# RaspberryPi4_shield.net
KiCad netlist of a schematic drawn in Altium Designer
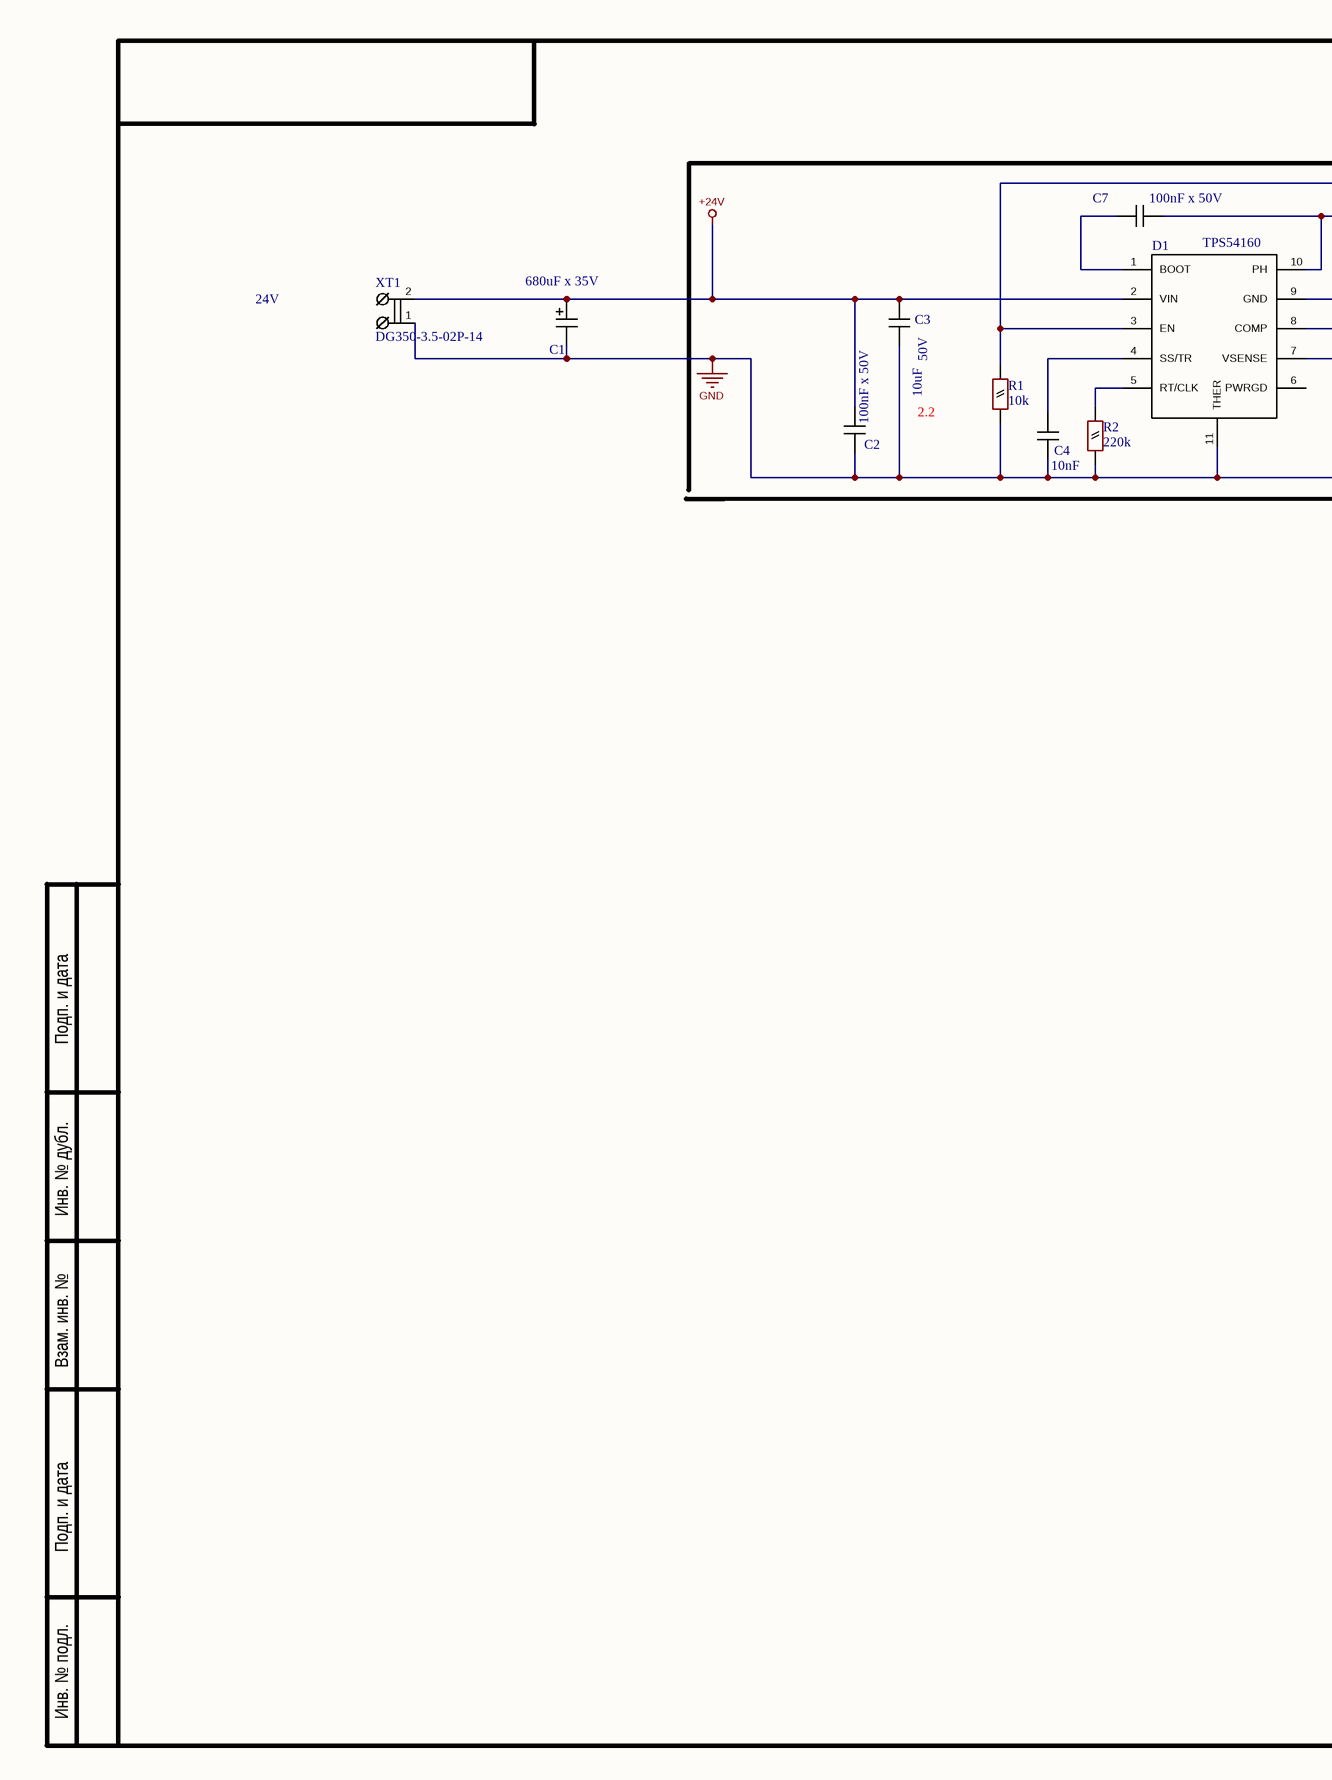
[diagram p0: RaspberryPi4_shield.SchDoc, left]
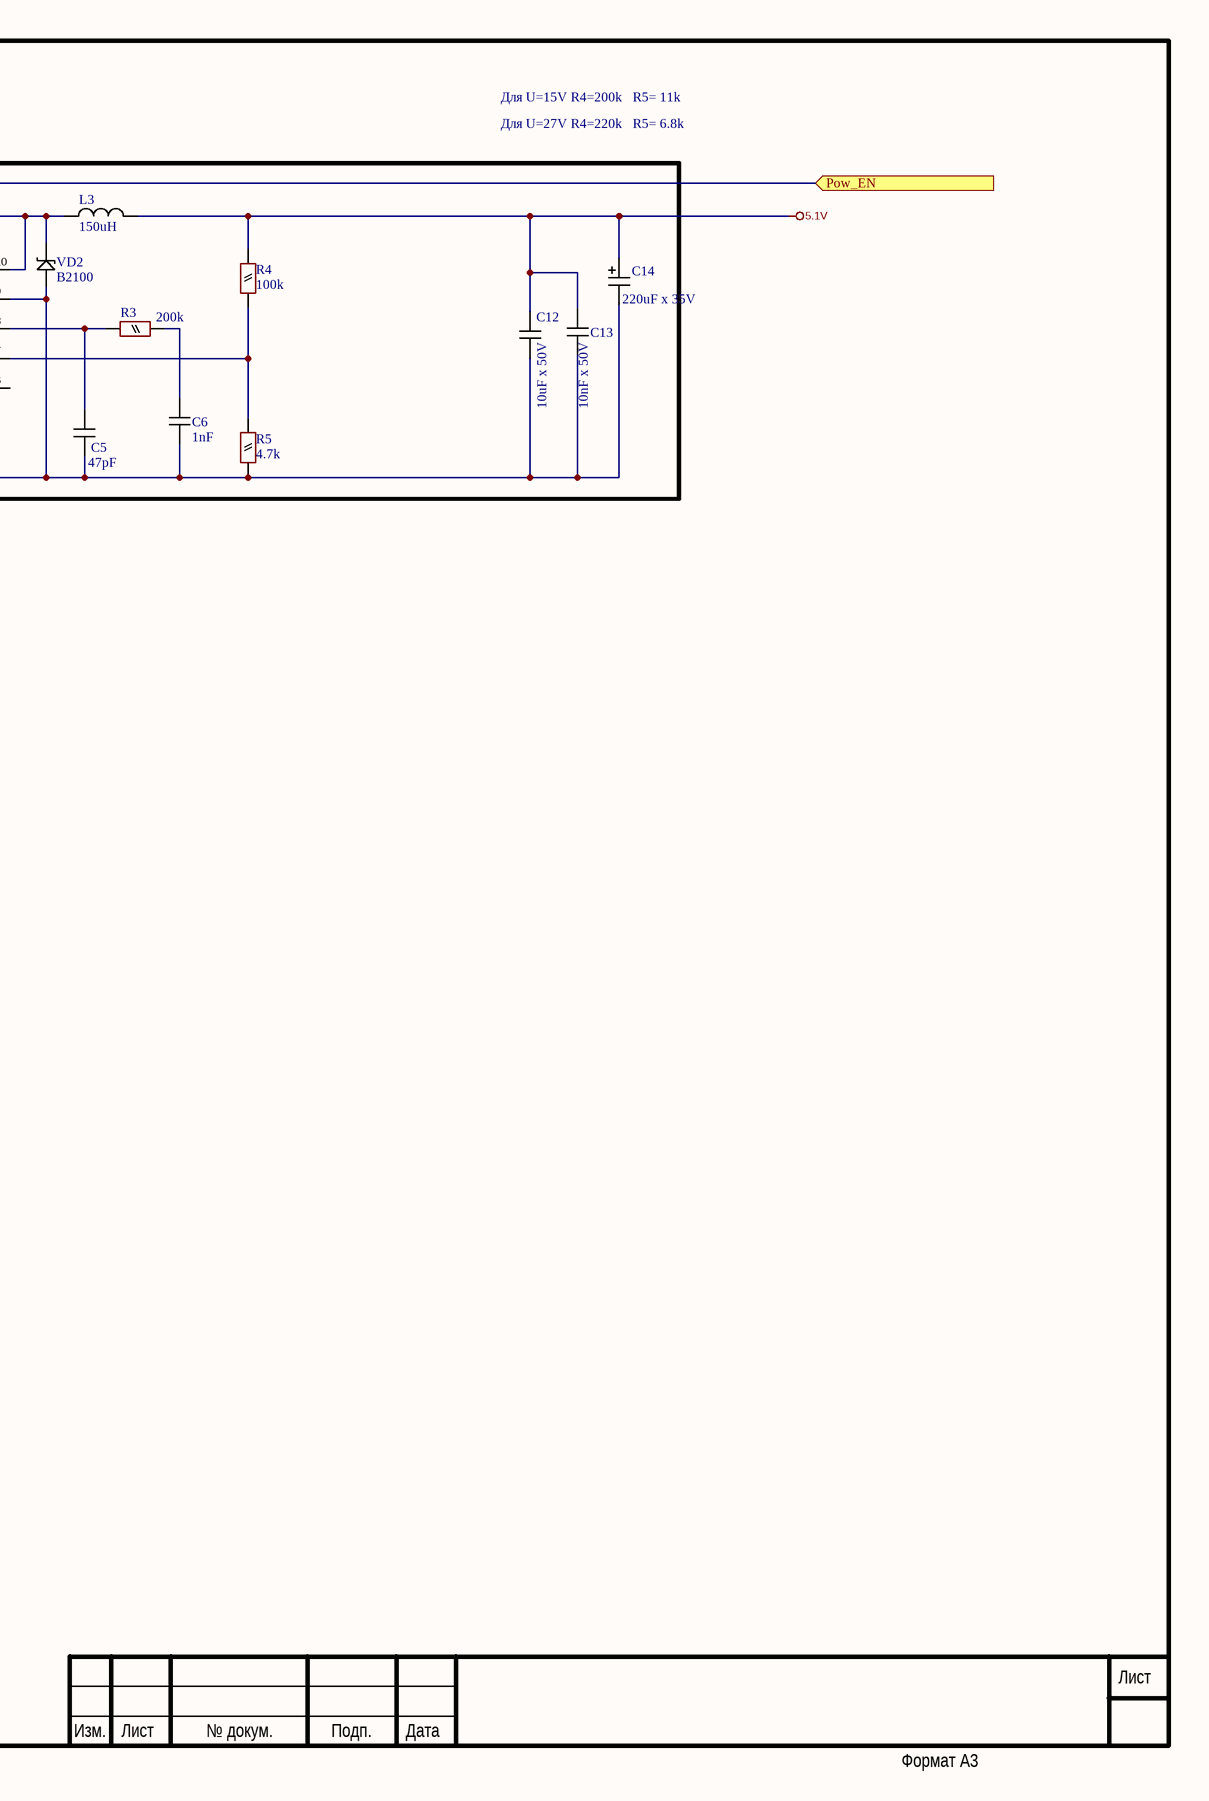
[diagram p1: RaspberryPi4_shield.SchDoc, right]

(export (version "E")
  (design (tool "Eeschema 10.0.6"))
  (components
    (comp (ref "C1")
      (value "680uF x 35V")
      (footprint "CAP_P_DIP-10x20")
      (description "Capasitor polar Dip")
      (libsource (lib "Gross") (part "CAPPOL_Dip"))
    )
    (comp (ref "C2")
      (value "100nF x 50V")
      (footprint "CAPSMD-0402")
      (description "Capasitor not polar")
      (fields (field (name "TOLERANCE") "X7R"))
      (libsource (lib "Gross") (part "CAPNPOL"))
    )
    (comp (ref "C3")
      (value "10uF")
      (footprint "CAPSMD-1206")
      (description "Capasitor not polar")
      (fields
        (field (name "POWER/VOLTAGE") "50V")
        (field (name "TOLERANCE") "X7R")
        (field (name "Comment") "CL31B106KBHNNNE")
      )
      (libsource (lib "Gross") (part "CAPNPOL"))
    )
    (comp (ref "C4")
      (value "10nF")
      (footprint "CAPSMD-0402")
      (description "Capasitor not polar")
      (fields (field (name "TOLERANCE") "X7R"))
      (libsource (lib "Gross") (part "CAPNPOL"))
    )
    (comp (ref "C5")
      (value "47pF")
      (footprint "CAPSMD-0402")
      (description "Capasitor not polar")
      (fields (field (name "TOLERANCE") "X7R"))
      (libsource (lib "Gross") (part "CAPNPOL"))
    )
    (comp (ref "C6")
      (value "1nF")
      (footprint "CAPSMD-0402")
      (description "Capasitor not polar")
      (fields (field (name "TOLERANCE") "X7R"))
      (libsource (lib "Gross") (part "CAPNPOL"))
    )
    (comp (ref "C7")
      (value "100nF x 50V")
      (footprint "CAPSMD-0402")
      (description "Capasitor not polar")
      (fields (field (name "TOLERANCE") "X7R"))
      (libsource (lib "Gross") (part "CAPNPOL"))
    )
    (comp (ref "C12")
      (value "10uF x 50V")
      (footprint "CAPSMD-1206")
      (description "Capasitor not polar")
      (fields (field (name "TOLERANCE") "X7R"))
      (libsource (lib "Gross") (part "CAPNPOL"))
    )
    (comp (ref "C13")
      (value "10nF x 50V")
      (footprint "CAPSMD-0402")
      (description "Capasitor not polar smd")
      (fields (field (name "TOLERANCE") "X7R"))
      (libsource (lib "Gross") (part "CAPNPOL"))
    )
    (comp (ref "C14")
      (value "220uF x 35V")
      (footprint "CAP_P_DIP-8x12")
      (description "Capasitor polar")
      (libsource (lib "Gross") (part "CAPPOL"))
    )
    (comp (ref "D1")
      (value "TPS54160")
      (footprint "MSOP10")
      (description "DC/DC Contoller")
      (fields (field (name "MANUFACTURERPARTNUMBER") "TPS54160DGQ"))
      (libsource (lib "Gross") (part "TPS54260"))
    )
    (comp (ref "L3")
      (value "150uH")
      (footprint "L_Ind_smd_MSS1260")
      (description "Inductor in SMD package")
      (fields (field (name "Comment") "INDUCTOR"))
      (libsource (lib "Gross") (part "INDUCTOR"))
    )
    (comp (ref "R1")
      (value "10k")
      (footprint "RESSMD-0402")
      (description "Resistor")
      (fields (field (name "TOLERANCE") "10%"))
      (libsource (lib "Gross") (part "RES0125"))
    )
    (comp (ref "R2")
      (value "220k")
      (footprint "RESSMD-0402")
      (description "Resistor")
      (fields (field (name "TOLERANCE") "10%"))
      (libsource (lib "Gross") (part "RES0125"))
    )
    (comp (ref "R3")
      (value "200k")
      (footprint "RESSMD-0402")
      (description "Resistor")
      (fields (field (name "TOLERANCE") "10%"))
      (libsource (lib "") (part "RES0125_1"))
    )
    (comp (ref "R4")
      (value "100k")
      (footprint "RESSMD-0402")
      (description "Resistor")
      (fields (field (name "TOLERANCE") "10%"))
      (libsource (lib "Gross") (part "RES0125"))
    )
    (comp (ref "R5")
      (value "4.7k")
      (footprint "RESSMD-0402")
      (description "Resistor")
      (fields (field (name "TOLERANCE") "10%"))
      (libsource (lib "Gross") (part "RES0125"))
    )
    (comp (ref "VD2")
      (value "B2100")
      (footprint "SMB (CASE-403C-01)")
      (description "SMD Diode Shotki")
      (libsource (lib "Gross") (part "Diode Shotki"))
    )
    (comp (ref "XT1")
      (value "DG350-3.5-02P-14")
      (footprint "Gross:DG350-3.5-02P-14")
      (libsource (lib "Gross") (part "DG350-3.5-02P-14"))
    )
  )
  (nets
    (net (code "1") (name "+24V") (class "Default")
      (node (ref "C1") (pin "1") (pinfunction "1_1") (pintype "passive"))
      (node (ref "C2") (pin "2") (pinfunction "2_2") (pintype "passive"))
      (node (ref "C3") (pin "2") (pinfunction "2_2") (pintype "passive"))
      (node (ref "D1") (pin "2") (pinfunction "VIN_2") (pintype "passive"))
      (node (ref "XT1") (pin "2") (pintype "passive"))
    )
    (net (code "2") (name "/Pow_EN") (class "Default")
      (node (ref "D1") (pin "3") (pinfunction "EN_3") (pintype "passive"))
      (node (ref "R1") (pin "2") (pinfunction "2_2") (pintype "passive"))
    )
    (net (code "3") (name "5.1V") (class "Default")
      (node (ref "C12") (pin "2") (pinfunction "2_2") (pintype "passive"))
      (node (ref "C13") (pin "2") (pinfunction "2_2") (pintype "passive"))
      (node (ref "C14") (pin "1") (pinfunction "1_1") (pintype "passive"))
      (node (ref "L3") (pin "2") (pinfunction "1_2") (pintype "passive"))
      (node (ref "R4") (pin "2") (pinfunction "2_2") (pintype "passive"))
    )
    (net (code "4") (name "GND") (class "Default")
      (node (ref "C1") (pin "2") (pinfunction "2_2") (pintype "passive"))
      (node (ref "C12") (pin "1") (pinfunction "1_1") (pintype "passive"))
      (node (ref "C13") (pin "1") (pinfunction "1_1") (pintype "passive"))
      (node (ref "C14") (pin "2") (pinfunction "2_2") (pintype "passive"))
      (node (ref "C2") (pin "1") (pinfunction "1_1") (pintype "passive"))
      (node (ref "C3") (pin "1") (pinfunction "1_1") (pintype "passive"))
      (node (ref "C4") (pin "1") (pinfunction "1_1") (pintype "passive"))
      (node (ref "C5") (pin "1") (pinfunction "1_1") (pintype "passive"))
      (node (ref "C6") (pin "1") (pinfunction "1_1") (pintype "passive"))
      (node (ref "D1") (pin "11") (pinfunction "THER_11") (pintype "passive"))
      (node (ref "D1") (pin "9") (pinfunction "GND_9") (pintype "passive"))
      (node (ref "R1") (pin "1") (pinfunction "1_1") (pintype "passive"))
      (node (ref "R2") (pin "1") (pinfunction "1_1") (pintype "passive"))
      (node (ref "R5") (pin "1") (pinfunction "1_1") (pintype "passive"))
      (node (ref "VD2") (pin "1") (pinfunction "A_1") (pintype "passive"))
      (node (ref "XT1") (pin "1") (pintype "passive"))
    )
    (net (code "5") (name "Net-(C6-Pad2)") (class "Default")
      (node (ref "C6") (pin "2") (pinfunction "2_2") (pintype "passive"))
      (node (ref "R3") (pin "2") (pinfunction "2_2") (pintype "passive"))
    )
    (net (code "6") (name "Net-(D1-BOOT)") (class "Default")
      (node (ref "C7") (pin "2") (pinfunction "2_2") (pintype "passive"))
      (node (ref "D1") (pin "1") (pinfunction "BOOT_1") (pintype "passive"))
    )
    (net (code "7") (name "Net-(D1-COMP)") (class "Default")
      (node (ref "C5") (pin "2") (pinfunction "2_2") (pintype "passive"))
      (node (ref "D1") (pin "8") (pinfunction "COMP_8") (pintype "passive"))
      (node (ref "R3") (pin "1") (pinfunction "1_1") (pintype "passive"))
    )
    (net (code "8") (name "Net-(D1-PH)") (class "Default")
      (node (ref "C7") (pin "1") (pinfunction "1_1") (pintype "passive"))
      (node (ref "D1") (pin "10") (pinfunction "PH_10") (pintype "passive"))
      (node (ref "L3") (pin "1") (pinfunction "0_1") (pintype "passive"))
      (node (ref "VD2") (pin "2") (pinfunction "C_2") (pintype "passive"))
    )
    (net (code "9") (name "Net-(D1-RT{slash}CLK)") (class "Default")
      (node (ref "D1") (pin "5") (pinfunction "RT/CLK_5") (pintype "passive"))
      (node (ref "R2") (pin "2") (pinfunction "2_2") (pintype "passive"))
    )
    (net (code "10") (name "Net-(D1-SS{slash}TR)") (class "Default")
      (node (ref "C4") (pin "2") (pinfunction "2_2") (pintype "passive"))
      (node (ref "D1") (pin "4") (pinfunction "SS/TR_4") (pintype "passive"))
    )
    (net (code "11") (name "Net-(D1-VSENSE)") (class "Default")
      (node (ref "D1") (pin "7") (pinfunction "VSENSE_7") (pintype "passive"))
      (node (ref "R4") (pin "1") (pinfunction "1_1") (pintype "passive"))
      (node (ref "R5") (pin "2") (pinfunction "2_2") (pintype "passive"))
    )
    (net (code "12") (name "unconnected-(D1-PWRGD-Pad6)") (class "Default")
      (node (ref "D1") (pin "6") (pinfunction "PWRGD_6") (pintype "passive"))
    )
  )
)
